# design.net
KiCad netlist of a schematic drawn in EasyEDA Pro
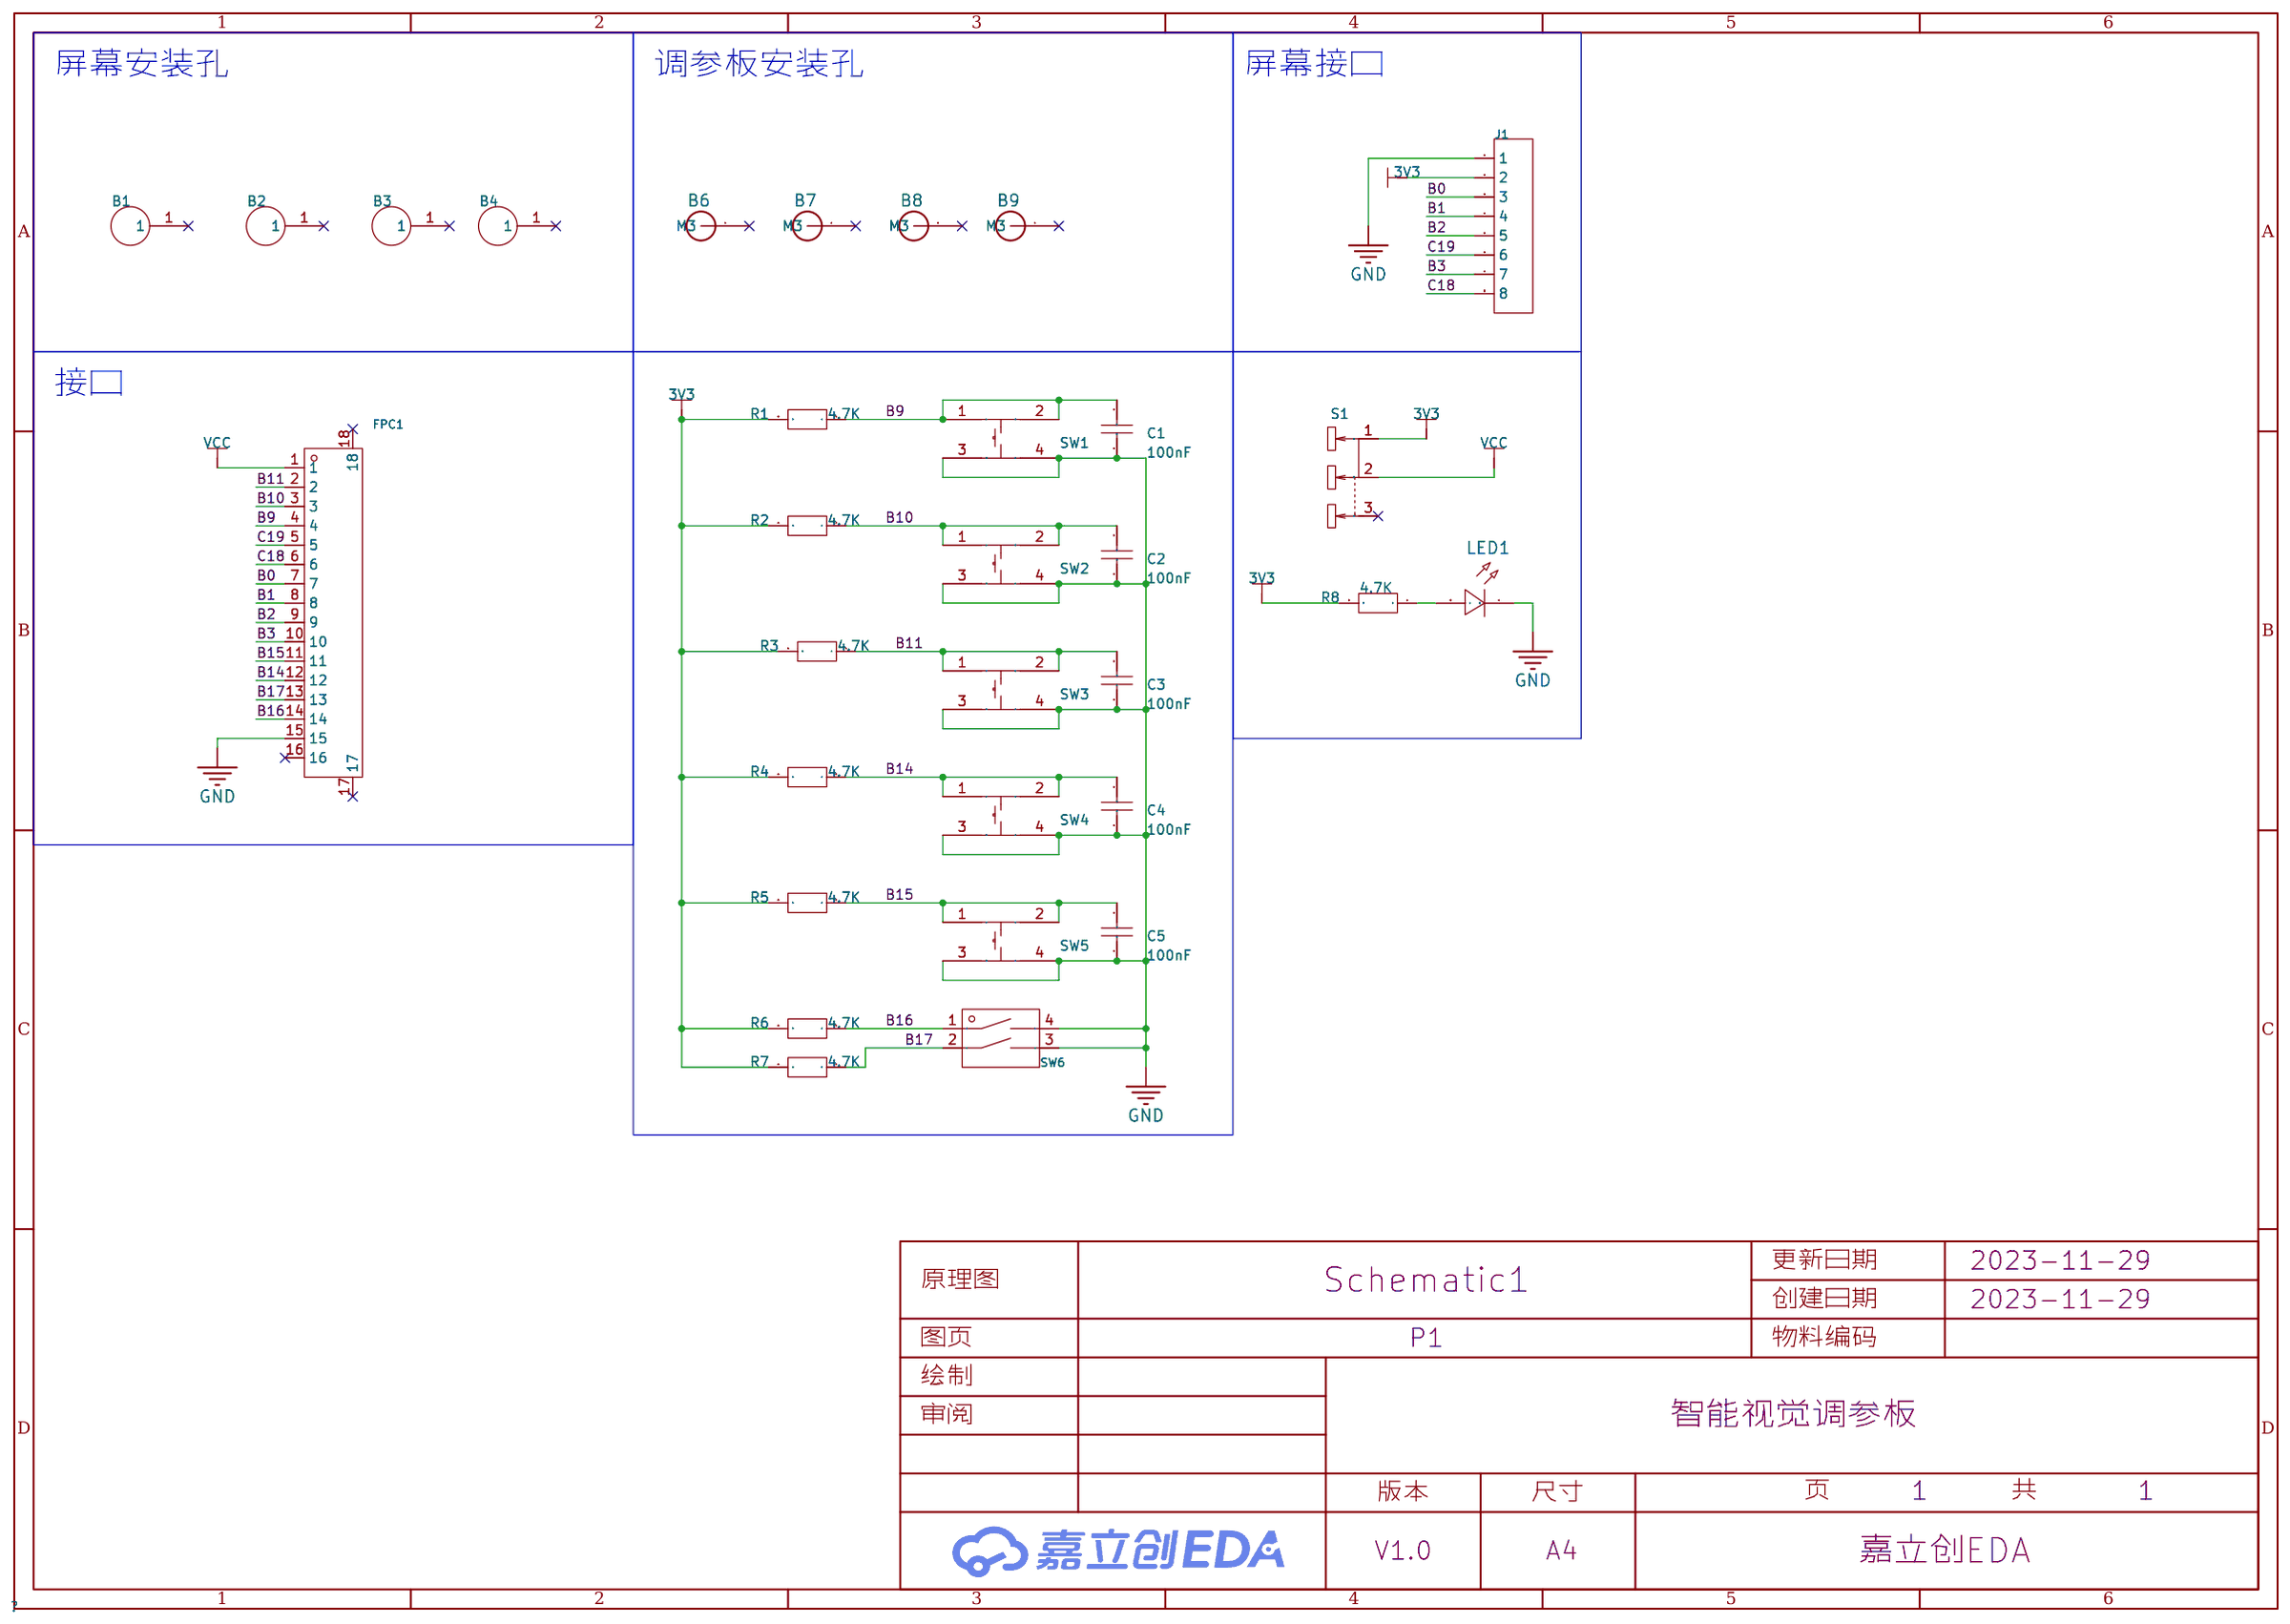
[diagram p0: schematic sheet]

(export (version "E")
  (design (tool "Eeschema 10.0.6"))
  (components
    (comp (ref "B1") (value "~") (footprint "easyedapro:M2") (libsource (lib "easyedapro") (part "M2")))
    (comp (ref "B2") (value "~") (footprint "easyedapro:M2") (libsource (lib "easyedapro") (part "M2")))
    (comp (ref "B3") (value "~") (footprint "easyedapro:M2") (libsource (lib "easyedapro") (part "M2")))
    (comp (ref "B4") (value "~") (footprint "easyedapro:M2") (libsource (lib "easyedapro") (part "M2")))
    (comp (ref "B6")
      (value "M3螺柱孔_JX")
      (footprint "easyedapro:M3")
      (libsource (lib "easyedapro") (part "M3螺柱孔_JX"))
    )
    (comp (ref "B7")
      (value "M3螺柱孔_JX")
      (footprint "easyedapro:M3")
      (libsource (lib "easyedapro") (part "M3螺柱孔_JX"))
    )
    (comp (ref "B8")
      (value "M3螺柱孔_JX")
      (footprint "easyedapro:M3")
      (libsource (lib "easyedapro") (part "M3螺柱孔_JX"))
    )
    (comp (ref "B9")
      (value "M3螺柱孔_JX")
      (footprint "easyedapro:M3")
      (libsource (lib "easyedapro") (part "M3螺柱孔_JX"))
    )
    (comp (ref "C1")
      (value "100nF")
      (footprint "easyedapro:C0603")
      (description "容值:100nF;精度:±10%;额定电压:50V;材质(温度系数):X7R;")
      (fields (field (name "Manufacturer Part") "0603B104K500NT") (field (name "Manufacturer") "FH(风华)"))
      (libsource (lib "easyedapro") (part "0603B104K500NT"))
    )
    (comp (ref "C2")
      (value "100nF")
      (footprint "easyedapro:C0603")
      (description "容值:100nF;精度:±10%;额定电压:50V;材质(温度系数):X7R;")
      (fields (field (name "Manufacturer Part") "0603B104K500NT") (field (name "Manufacturer") "FH(风华)"))
      (libsource (lib "easyedapro") (part "0603B104K500NT"))
    )
    (comp (ref "C3")
      (value "100nF")
      (footprint "easyedapro:C0603")
      (description "容值:100nF;精度:±10%;额定电压:50V;材质(温度系数):X7R;")
      (fields (field (name "Manufacturer Part") "0603B104K500NT") (field (name "Manufacturer") "FH(风华)"))
      (libsource (lib "easyedapro") (part "0603B104K500NT"))
    )
    (comp (ref "C4")
      (value "100nF")
      (footprint "easyedapro:C0603")
      (description "容值:100nF;精度:±10%;额定电压:50V;材质(温度系数):X7R;")
      (fields (field (name "Manufacturer Part") "0603B104K500NT") (field (name "Manufacturer") "FH(风华)"))
      (libsource (lib "easyedapro") (part "0603B104K500NT"))
    )
    (comp (ref "C5")
      (value "100nF")
      (footprint "easyedapro:C0603")
      (description "容值:100nF;精度:±10%;额定电压:50V;材质(温度系数):X7R;")
      (fields (field (name "Manufacturer Part") "0603B104K500NT") (field (name "Manufacturer") "FH(风华)"))
      (libsource (lib "easyedapro") (part "0603B104K500NT"))
    )
    (comp (ref "FPC1")
      (value "FPC-05F-16PH20")
      (footprint "easyedapro:FPC-SMD_16P-P0.50_FPC-05F-16PH20")
      (description "间距:0.5mm;触点数量:16P;锁定特性:翻盖式;安装类型:卧贴;触点类型:下接;工作温度范围:-25°C~+85°C;")
      (fields (field (name "Manufacturer") "XUNPU(讯普)"))
      (libsource (lib "easyedapro") (part "FPC-05F-16PH20"))
    )
    (comp (ref "J1")
      (value "~")
      (footprint "easyedapro:HDR-TH_8P-P2.54-V-F-1")
      (libsource (lib "easyedapro") (part "Header-Female-2.54_1x8"))
    )
    (comp (ref "LED1")
      (value "~")
      (footprint "easyedapro:LED_0603")
      (libsource (lib "easyedapro") (part "LED_R"))
    )
    (comp (ref "R1")
      (value "4.7K")
      (footprint "easyedapro:R0603")
      (fields (field (name "Manufacturer Part") "0603"))
      (libsource (lib "easyedapro") (part "0603_C9900021181"))
    )
    (comp (ref "R2")
      (value "4.7K")
      (footprint "easyedapro:R0603")
      (fields (field (name "Manufacturer Part") "0603"))
      (libsource (lib "easyedapro") (part "0603_C9900021181"))
    )
    (comp (ref "R3")
      (value "4.7K")
      (footprint "easyedapro:R0603")
      (fields (field (name "Manufacturer Part") "0603"))
      (libsource (lib "easyedapro") (part "0603_C9900021181"))
    )
    (comp (ref "R4")
      (value "4.7K")
      (footprint "easyedapro:R0603")
      (fields (field (name "Manufacturer Part") "0603"))
      (libsource (lib "easyedapro") (part "0603_C9900021181"))
    )
    (comp (ref "R5")
      (value "4.7K")
      (footprint "easyedapro:R0603")
      (fields (field (name "Manufacturer Part") "0603"))
      (libsource (lib "easyedapro") (part "0603_C9900021181"))
    )
    (comp (ref "R6")
      (value "4.7K")
      (footprint "easyedapro:R0603")
      (fields (field (name "Manufacturer Part") "0603"))
      (libsource (lib "easyedapro") (part "0603_C9900021181"))
    )
    (comp (ref "R7")
      (value "4.7K")
      (footprint "easyedapro:R0603")
      (fields (field (name "Manufacturer Part") "0603"))
      (libsource (lib "easyedapro") (part "0603_C9900021181"))
    )
    (comp (ref "R8")
      (value "4.7K")
      (footprint "easyedapro:R0603")
      (fields (field (name "Manufacturer Part") "0603"))
      (libsource (lib "easyedapro") (part "0603_C9900021181"))
    )
    (comp (ref "S1")
      (value "SS-12D10L3")
      (footprint "easyedapro:SW-TH_SS-12D10L3")
      (description "额定电流(DC):3A;额定电压(DC):125V;额定电流(AC):3A;额定电压(AC):125V;电路结构:单刀双掷;安装方式:直插;机械寿命:1万次;开关颜色:黑色;")
      (fields (field (name "Manufacturer") "XKB Connectivity(中国星坤)"))
      (libsource (lib "easyedapro") (part "SS-12D10L3"))
    )
    (comp (ref "SW1")
      (value "TS-1002S-05026C")
      (footprint "easyedapro:KEY-SMD_4P-L6.0-W6.0-P4.50-LS9.0")
      (description "电路结构:单刀单掷;触点电流:50mA;额定电压(DC):12V;安装方式:立贴;带灯:-;机械寿命:-;")
      (fields (field (name "Manufacturer") "XUNPU(讯普)"))
      (libsource (lib "easyedapro") (part "TS-1002S-05026C"))
    )
    (comp (ref "SW2")
      (value "TS-1002S-05026C")
      (footprint "easyedapro:KEY-SMD_4P-L6.0-W6.0-P4.50-LS9.0")
      (description "电路结构:单刀单掷;触点电流:50mA;额定电压(DC):12V;安装方式:立贴;带灯:-;机械寿命:-;")
      (fields (field (name "Manufacturer") "XUNPU(讯普)"))
      (libsource (lib "easyedapro") (part "TS-1002S-05026C"))
    )
    (comp (ref "SW3")
      (value "TS-1002S-05026C")
      (footprint "easyedapro:KEY-SMD_4P-L6.0-W6.0-P4.50-LS9.0")
      (description "电路结构:单刀单掷;触点电流:50mA;额定电压(DC):12V;安装方式:立贴;带灯:-;机械寿命:-;")
      (fields (field (name "Manufacturer") "XUNPU(讯普)"))
      (libsource (lib "easyedapro") (part "TS-1002S-05026C"))
    )
    (comp (ref "SW4")
      (value "TS-1002S-05026C")
      (footprint "easyedapro:KEY-SMD_4P-L6.0-W6.0-P4.50-LS9.0")
      (description "电路结构:单刀单掷;触点电流:50mA;额定电压(DC):12V;安装方式:立贴;带灯:-;机械寿命:-;")
      (fields (field (name "Manufacturer") "XUNPU(讯普)"))
      (libsource (lib "easyedapro") (part "TS-1002S-05026C"))
    )
    (comp (ref "SW5")
      (value "TS-1002S-05026C")
      (footprint "easyedapro:KEY-SMD_4P-L6.0-W6.0-P4.50-LS9.0")
      (description "电路结构:单刀单掷;触点电流:50mA;额定电压(DC):12V;安装方式:立贴;带灯:-;机械寿命:-;")
      (fields (field (name "Manufacturer") "XUNPU(讯普)"))
      (libsource (lib "easyedapro") (part "TS-1002S-05026C"))
    )
    (comp (ref "SW6")
      (value "KF1001-02P-R0-FL-ON-01B")
      (footprint "easyedapro:SW-TH_KF1001-02P-R0-FL-ON-01B")
      (description "拨码开关 平拨，凸起式 单刀单掷  2  2.54mm")
      (fields (field (name "Manufacturer") "凯峰"))
      (libsource (lib "easyedapro") (part "KF1001-02P-R0-FL-ON-01B"))
    )
  )
  (nets
    (net (code "1") (name "/B0") (class "Default")
      (node (ref "FPC1") (pin "7") (pinfunction "7_7") (pintype "input"))
      (node (ref "J1") (pin "3") (pinfunction "3_3") (pintype "input"))
    )
    (net (code "2") (name "/B1") (class "Default")
      (node (ref "FPC1") (pin "8") (pinfunction "8_8") (pintype "input"))
      (node (ref "J1") (pin "4") (pinfunction "4_4") (pintype "input"))
    )
    (net (code "3") (name "/B2") (class "Default")
      (node (ref "FPC1") (pin "9") (pinfunction "9_9") (pintype "input"))
      (node (ref "J1") (pin "5") (pinfunction "5_5") (pintype "input"))
    )
    (net (code "4") (name "/B3") (class "Default")
      (node (ref "FPC1") (pin "10") (pinfunction "10_10") (pintype "input"))
      (node (ref "J1") (pin "7") (pinfunction "7_7") (pintype "input"))
    )
    (net (code "5") (name "/B9") (class "Default")
      (node (ref "C1") (pin "2") (pinfunction "2_2") (pintype "input"))
      (node (ref "FPC1") (pin "4") (pinfunction "4_4") (pintype "input"))
      (node (ref "R1") (pin "1") (pinfunction "1_1") (pintype "input"))
      (node (ref "SW1") (pin "1") (pinfunction "1_1") (pintype "unspecified"))
      (node (ref "SW1") (pin "2") (pinfunction "2_2") (pintype "unspecified"))
    )
    (net (code "6") (name "/B10") (class "Default")
      (node (ref "C2") (pin "2") (pinfunction "2_2") (pintype "input"))
      (node (ref "FPC1") (pin "3") (pinfunction "3_3") (pintype "input"))
      (node (ref "R2") (pin "1") (pinfunction "1_1") (pintype "input"))
      (node (ref "SW2") (pin "1") (pinfunction "1_1") (pintype "unspecified"))
      (node (ref "SW2") (pin "2") (pinfunction "2_2") (pintype "unspecified"))
    )
    (net (code "7") (name "/B11") (class "Default")
      (node (ref "C3") (pin "2") (pinfunction "2_2") (pintype "input"))
      (node (ref "FPC1") (pin "2") (pinfunction "2_2") (pintype "input"))
      (node (ref "R3") (pin "1") (pinfunction "1_1") (pintype "input"))
      (node (ref "SW3") (pin "1") (pinfunction "1_1") (pintype "unspecified"))
      (node (ref "SW3") (pin "2") (pinfunction "2_2") (pintype "unspecified"))
    )
    (net (code "8") (name "/B14") (class "Default")
      (node (ref "C4") (pin "2") (pinfunction "2_2") (pintype "input"))
      (node (ref "FPC1") (pin "12") (pinfunction "12_12") (pintype "input"))
      (node (ref "R4") (pin "1") (pinfunction "1_1") (pintype "input"))
      (node (ref "SW4") (pin "1") (pinfunction "1_1") (pintype "unspecified"))
      (node (ref "SW4") (pin "2") (pinfunction "2_2") (pintype "unspecified"))
    )
    (net (code "9") (name "/B15") (class "Default")
      (node (ref "C5") (pin "2") (pinfunction "2_2") (pintype "input"))
      (node (ref "FPC1") (pin "11") (pinfunction "11_11") (pintype "input"))
      (node (ref "R5") (pin "1") (pinfunction "1_1") (pintype "input"))
      (node (ref "SW5") (pin "1") (pinfunction "1_1") (pintype "unspecified"))
      (node (ref "SW5") (pin "2") (pinfunction "2_2") (pintype "unspecified"))
    )
    (net (code "10") (name "/B16") (class "Default")
      (node (ref "FPC1") (pin "14") (pinfunction "14_14") (pintype "input"))
      (node (ref "R6") (pin "1") (pinfunction "1_1") (pintype "input"))
      (node (ref "SW6") (pin "1") (pinfunction "1_1") (pintype "input"))
    )
    (net (code "11") (name "/B17") (class "Default")
      (node (ref "FPC1") (pin "13") (pinfunction "13_13") (pintype "input"))
      (node (ref "R7") (pin "1") (pinfunction "1_1") (pintype "input"))
      (node (ref "SW6") (pin "2") (pinfunction "2_2") (pintype "input"))
    )
    (net (code "12") (name "/C18") (class "Default")
      (node (ref "FPC1") (pin "6") (pinfunction "6_6") (pintype "input"))
      (node (ref "J1") (pin "8") (pinfunction "8_8") (pintype "input"))
    )
    (net (code "13") (name "/C19") (class "Default")
      (node (ref "FPC1") (pin "5") (pinfunction "5_5") (pintype "input"))
      (node (ref "J1") (pin "6") (pinfunction "6_6") (pintype "input"))
    )
    (net (code "14") (name "3V3") (class "Default")
      (node (ref "J1") (pin "2") (pinfunction "2_2") (pintype "input"))
      (node (ref "R1") (pin "2") (pinfunction "2_2") (pintype "input"))
      (node (ref "R2") (pin "2") (pinfunction "2_2") (pintype "input"))
      (node (ref "R3") (pin "2") (pinfunction "2_2") (pintype "input"))
      (node (ref "R4") (pin "2") (pinfunction "2_2") (pintype "input"))
      (node (ref "R5") (pin "2") (pinfunction "2_2") (pintype "input"))
      (node (ref "R6") (pin "2") (pinfunction "2_2") (pintype "input"))
      (node (ref "R7") (pin "2") (pinfunction "2_2") (pintype "input"))
      (node (ref "R8") (pin "2") (pinfunction "2_2") (pintype "input"))
      (node (ref "S1") (pin "1") (pinfunction "1_1") (pintype "input"))
    )
    (net (code "15") (name "GND") (class "Default")
      (node (ref "C1") (pin "1") (pinfunction "1_1") (pintype "input"))
      (node (ref "C2") (pin "1") (pinfunction "1_1") (pintype "input"))
      (node (ref "C3") (pin "1") (pinfunction "1_1") (pintype "input"))
      (node (ref "C4") (pin "1") (pinfunction "1_1") (pintype "input"))
      (node (ref "C5") (pin "1") (pinfunction "1_1") (pintype "input"))
      (node (ref "FPC1") (pin "15") (pinfunction "15_15") (pintype "input"))
      (node (ref "J1") (pin "1") (pinfunction "1_1") (pintype "input"))
      (node (ref "LED1") (pin "1") (pinfunction "C_1") (pintype "input"))
      (node (ref "SW1") (pin "3") (pinfunction "3_3") (pintype "unspecified"))
      (node (ref "SW1") (pin "4") (pinfunction "4_4") (pintype "unspecified"))
      (node (ref "SW2") (pin "3") (pinfunction "3_3") (pintype "unspecified"))
      (node (ref "SW2") (pin "4") (pinfunction "4_4") (pintype "unspecified"))
      (node (ref "SW3") (pin "3") (pinfunction "3_3") (pintype "unspecified"))
      (node (ref "SW3") (pin "4") (pinfunction "4_4") (pintype "unspecified"))
      (node (ref "SW4") (pin "3") (pinfunction "3_3") (pintype "unspecified"))
      (node (ref "SW4") (pin "4") (pinfunction "4_4") (pintype "unspecified"))
      (node (ref "SW5") (pin "3") (pinfunction "3_3") (pintype "unspecified"))
      (node (ref "SW5") (pin "4") (pinfunction "4_4") (pintype "unspecified"))
      (node (ref "SW6") (pin "3") (pinfunction "3_3") (pintype "input"))
      (node (ref "SW6") (pin "4") (pinfunction "4_4") (pintype "input"))
    )
    (net (code "16") (name "Net-(LED1-A)") (class "Default")
      (node (ref "LED1") (pin "2") (pinfunction "A_2") (pintype "input"))
      (node (ref "R8") (pin "1") (pinfunction "1_1") (pintype "input"))
    )
    (net (code "17") (name "VCC") (class "Default")
      (node (ref "FPC1") (pin "1") (pinfunction "1_1") (pintype "input"))
      (node (ref "S1") (pin "2") (pinfunction "2_2") (pintype "input"))
    )
    (net (code "18") (name "unconnected-(B1-Pad1)") (class "Default")
      (node (ref "B1") (pin "1") (pinfunction "1_1") (pintype "input+no_connect"))
    )
    (net (code "19") (name "unconnected-(B2-Pad1)") (class "Default")
      (node (ref "B2") (pin "1") (pinfunction "1_1") (pintype "input+no_connect"))
    )
    (net (code "20") (name "unconnected-(B3-Pad1)") (class "Default")
      (node (ref "B3") (pin "1") (pinfunction "1_1") (pintype "input+no_connect"))
    )
    (net (code "21") (name "unconnected-(B4-Pad1)") (class "Default")
      (node (ref "B4") (pin "1") (pinfunction "1_1") (pintype "input+no_connect"))
    )
    (net (code "22") (name "unconnected-(B6-M3-Pad1)") (class "Default")
      (node (ref "B6") (pin "1") (pinfunction "M3_1") (pintype "input+no_connect"))
    )
    (net (code "23") (name "unconnected-(B7-M3-Pad1)") (class "Default")
      (node (ref "B7") (pin "1") (pinfunction "M3_1") (pintype "input+no_connect"))
    )
    (net (code "24") (name "unconnected-(B8-M3-Pad1)") (class "Default")
      (node (ref "B8") (pin "1") (pinfunction "M3_1") (pintype "input+no_connect"))
    )
    (net (code "25") (name "unconnected-(B9-M3-Pad1)") (class "Default")
      (node (ref "B9") (pin "1") (pinfunction "M3_1") (pintype "input+no_connect"))
    )
    (net (code "26") (name "unconnected-(FPC1-Pad16)") (class "Default")
      (node (ref "FPC1") (pin "16") (pinfunction "16_16") (pintype "input+no_connect"))
    )
    (net (code "27") (name "unconnected-(FPC1-Pad17)") (class "Default")
      (node (ref "FPC1") (pin "17") (pinfunction "17_17") (pintype "input+no_connect"))
    )
    (net (code "28") (name "unconnected-(FPC1-Pad18)") (class "Default")
      (node (ref "FPC1") (pin "18") (pinfunction "18_18") (pintype "input+no_connect"))
    )
    (net (code "29") (name "unconnected-(S1-Pad3)") (class "Default")
      (node (ref "S1") (pin "3") (pinfunction "3_3") (pintype "input+no_connect"))
    )
  )
)
